# al115v20_power.net
KiCad netlist of a schematic drawn in Altium Designer
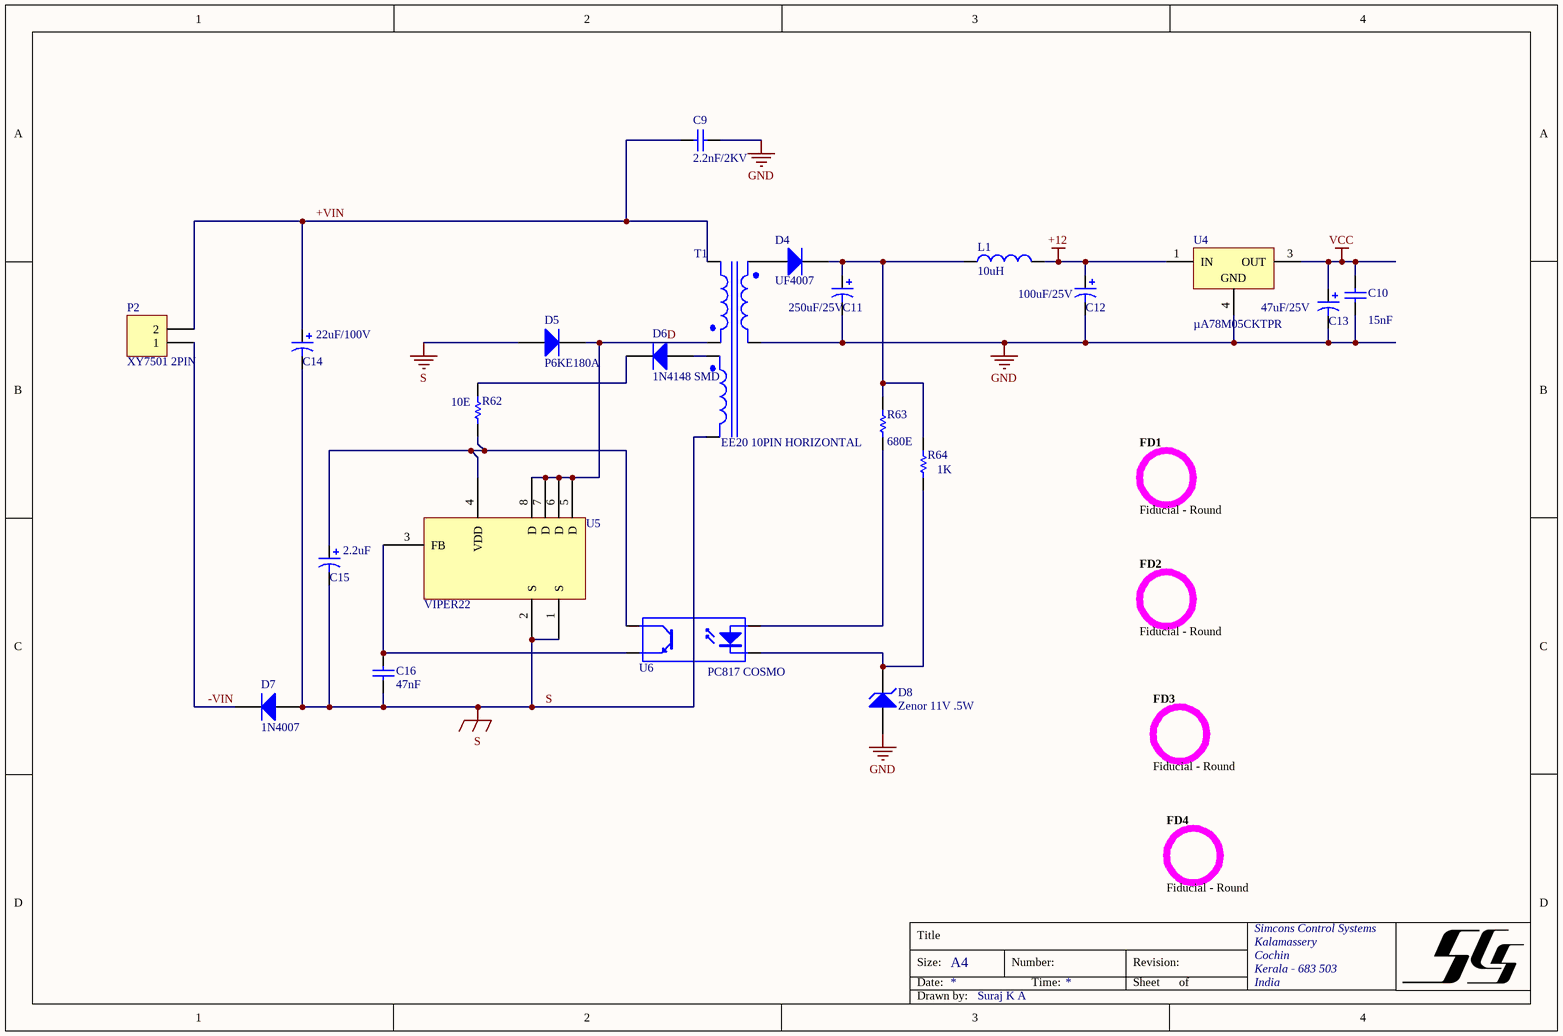
[diagram p0: al115v20_power.SchDoc]

(export (version "E")
  (design (tool "Eeschema 10.0.6"))
  (components
    (comp (ref "C9")
      (value "2.2nF/2KV")
      (footprint "CAP DISC .2")
      (description "Capacitor")
      (fields (field (name "Comment") "2.2nF/2kV") (field (name "PUBLISHER") "Altium Limited"))
      (libsource (lib "Miscellaneous Devices") (part "Cap"))
    )
    (comp (ref "C10")
      (value "15nF")
      (footprint "C1206")
      (description "Capacitor")
      (fields (field (name "Comment") ".1uF 1206") (field (name "PUBLISHER") "Altium Limited"))
      (libsource (lib "Miscellaneous Devices") (part "Cap"))
    )
    (comp (ref "C11")
      (value "250uF/25V")
      (footprint "Cap_.2")
      (description "Polarized Capacitor (Radial)")
      (fields (field (name "Comment") "470uF/25V") (field (name "PUBLISHER") "Altium Limited"))
      (libsource (lib "Miscellaneous Devices") (part "Cap Pol1"))
    )
    (comp (ref "C12")
      (value "100uF/25V")
      (footprint "Cap_.6.3x11x2.5")
      (description "Polarized Capacitor (Radial)")
      (fields (field (name "PUBLISHER") "Altium Limited"))
      (libsource (lib "Miscellaneous Devices") (part "Cap Pol1"))
    )
    (comp (ref "C13")
      (value "47uF/25V")
      (footprint "Cap_.6.3x11x2.5")
      (description "Polarized Capacitor (Radial)")
      (fields (field (name "Comment") "100uF/25V") (field (name "PUBLISHER") "Altium Limited"))
      (libsource (lib "Miscellaneous Devices") (part "Cap Pol1"))
    )
    (comp (ref "C14")
      (value "22uF/100V")
      (footprint "Cap_.2")
      (description "Polarized Capacitor (Radial)")
      (fields (field (name "PUBLISHER") "Altium Limited"))
      (libsource (lib "Miscellaneous Devices") (part "Cap Pol1"))
    )
    (comp (ref "C15")
      (value "2.2uF")
      (footprint "Cap_.1")
      (description "Polarized Capacitor (Radial)")
      (fields (field (name "Comment") "10uF/63V") (field (name "PUBLISHER") "Altium Limited"))
      (libsource (lib "Miscellaneous Devices") (part "Cap Pol1"))
    )
    (comp (ref "C16")
      (value "47nF")
      (footprint "C1206")
      (description "Capacitor")
      (fields (field (name "Comment") "47nF 1206") (field (name "PUBLISHER") "Altium Limited"))
      (libsource (lib "Miscellaneous Devices") (part "Cap"))
    )
    (comp (ref "D4")
      (value "UF4007")
      (footprint "DIODE1A")
      (description "Default Diode")
      (fields (field (name "PUBLISHER") "Altium Limited"))
      (libsource (lib "Miscellaneous Devices") (part "Diode"))
    )
    (comp (ref "D5")
      (value "P6KE180A")
      (footprint "DIODE1A")
      (description "Default Diode")
      (fields (field (name "PUBLISHER") "Altium Limited"))
      (libsource (lib "Miscellaneous Devices") (part "Diode"))
    )
    (comp (ref "D6")
      (value "1N4148 SMD")
      (footprint "4148SMDW")
      (description "Default Diode")
      (fields (field (name "PUBLISHER") "Altium Limited"))
      (libsource (lib "Miscellaneous Devices") (part "Diode"))
    )
    (comp (ref "D7")
      (value "1N4007")
      (footprint "DIODE1A")
      (description "Default Diode")
      (fields (field (name "PUBLISHER") "Altium Limited"))
      (libsource (lib "Miscellaneous Devices") (part "Diode"))
    )
    (comp (ref "D8")
      (value "Zenor 11V .5W")
      (footprint "DZENOR .25W - duplicate")
      (description "Zener Diode")
      (fields (field (name "PUBLISHER") "Altium Limited"))
      (libsource (lib "Miscellaneous Devices") (part "D Zener"))
    )
    (comp (ref "FD1")
      (value "Fiducial - Round")
      (footprint "FIDUCIAL 2mm")
      (description "Fiducial - Round 1.5mm Top-Bottom")
      (libsource (lib "PCB_Project1") (part "FIDUCIAL ROUND"))
    )
    (comp (ref "FD2")
      (value "Fiducial - Round")
      (footprint "FIDUCIAL 2mm")
      (description "Fiducial - Round 1.5mm Top-Bottom")
      (libsource (lib "PCB_Project1") (part "FIDUCIAL ROUND"))
    )
    (comp (ref "FD3")
      (value "Fiducial - Round")
      (footprint "FIDUCIAL 2MM")
      (description "Fiducial - Round 1.5mm Top-Bottom")
      (libsource (lib "PCB_Project1") (part "FIDUCIAL ROUND"))
    )
    (comp (ref "FD4")
      (value "Fiducial - Round")
      (footprint "FIDUCIAL 2MM")
      (description "Fiducial - Round 1.5mm Top-Bottom")
      (libsource (lib "PCB_Project1") (part "FIDUCIAL ROUND"))
    )
    (comp (ref "L1")
      (value "10uH")
      (footprint "INDUCTOR 5x8")
      (description "Inductor")
      (fields (field (name "Comment") "Inductor 10uH Drum Core") (field (name "PUBLISHER") "Altium Limited"))
      (libsource (lib "Miscellaneous Devices") (part "Inductor"))
    )
    (comp (ref "P2")
      (value "XY7501 2PIN")
      (footprint "XY7501_7.62_2PIN")
      (description "Header, 2-Pin")
      (fields (field (name "PUBLISHER") "Altium Limited"))
      (libsource (lib "Miscellaneous Connectors") (part "Header 2"))
    )
    (comp (ref "R62")
      (value "10E")
      (footprint "R1206")
      (description "Semiconductor Resistor")
      (fields (field (name "Comment") "10E 1206") (field (name "PUBLISHER") "Altium Limited"))
      (libsource (lib "Miscellaneous Devices") (part "Res Semi"))
    )
    (comp (ref "R63")
      (value "680E")
      (footprint "R1206")
      (description "Resistor")
      (fields (field (name "Comment") "100E 1206") (field (name "PUBLISHER") "Altium Limited"))
      (libsource (lib "Miscellaneous Devices") (part "Res1"))
    )
    (comp (ref "R64")
      (value "1K")
      (footprint "R1206")
      (description "Resistor")
      (fields (field (name "Comment") "1K 1206") (field (name "PUBLISHER") "Altium Limited"))
      (libsource (lib "Miscellaneous Devices") (part "Res1"))
    )
    (comp (ref "T1")
      (value "EE20 10PIN HORIZONTAL")
      (footprint "EE20_HOR_10PIN")
      (description "Three-winding Transformer (Switching")
      (fields (field (name "PUBLISHER") "Altium Limited"))
      (libsource (lib "PCB_Project1") (part "TransSwitching"))
    )
    (comp (ref "U4")
      (value "µA78M05CKTPR")
      (footprint "TO252AA")
      (description "Positive-Voltage Regulator")
      (fields (field (name "PUBLISHER") "Altium Limited"))
      (libsource (lib "TI Power Mgt Voltage Regulator") (part "µA78M05CKTPR"))
    )
    (comp (ref "U5")
      (value "VIPER22")
      (footprint "DIP-8_S")
      (fields (field (name "MANUFACTURER") "Power Integrations"))
      (libsource (lib "PCB_Project1") (part "VIPER22"))
    )
    (comp (ref "U6")
      (value "PC817 COSMO")
      (footprint "DIP-4_S")
      (description "4-Pin Phototransistor Optocoupler")
      (fields (field (name "PUBLISHER") "Altium Limited"))
      (libsource (lib "Miscellaneous Devices") (part "Optoisolator1"))
    )
  )
  (nets
    (net (code "1") (name "+12") (class "Default")
      (node (ref "C12") (pin "1") (pinfunction "1_1") (pintype "passive"))
      (node (ref "L1") (pin "2") (pinfunction "2_2") (pintype "passive"))
      (node (ref "U4") (pin "1") (pinfunction "IN_1") (pintype "power_in"))
    )
    (net (code "2") (name "/+VIN") (class "Default")
      (node (ref "C14") (pin "1") (pinfunction "1_1") (pintype "passive"))
      (node (ref "C9") (pin "2") (pinfunction "2_2") (pintype "passive"))
      (node (ref "P2") (pin "2") (pinfunction "2_2") (pintype "passive"))
      (node (ref "T1") (pin "1") (pinfunction "Pri+_1") (pintype "passive"))
    )
    (net (code "3") (name "/-VIN") (class "Default")
      (node (ref "D7") (pin "2") (pinfunction "K_2") (pintype "passive"))
      (node (ref "P2") (pin "1") (pinfunction "1_1") (pintype "passive"))
    )
    (net (code "4") (name "/D") (class "Default")
      (node (ref "D5") (pin "2") (pinfunction "K_2") (pintype "passive"))
      (node (ref "T1") (pin "2") (pinfunction "Pri-_2") (pintype "passive"))
      (node (ref "U5") (pin "5") (pinfunction "D_5") (pintype "passive"))
      (node (ref "U5") (pin "6") (pinfunction "D_6") (pintype "passive"))
      (node (ref "U5") (pin "7") (pinfunction "D_7") (pintype "passive"))
      (node (ref "U5") (pin "8") (pinfunction "D_8") (pintype "passive"))
    )
    (net (code "5") (name "GND") (class "Default")
      (node (ref "C10") (pin "1") (pinfunction "1_1") (pintype "passive"))
      (node (ref "C11") (pin "2") (pinfunction "2_2") (pintype "passive"))
      (node (ref "C12") (pin "2") (pinfunction "2_2") (pintype "passive"))
      (node (ref "C13") (pin "2") (pinfunction "2_2") (pintype "passive"))
      (node (ref "C9") (pin "1") (pinfunction "1_1") (pintype "passive"))
      (node (ref "D8") (pin "1") (pinfunction "A_1") (pintype "passive"))
      (node (ref "T1") (pin "7") (pinfunction "Sec1-_7") (pintype "passive"))
      (node (ref "U4") (pin "4") (pinfunction "GND_4") (pintype "power_in"))
    )
    (net (code "6") (name "Net-(D4-A)") (class "Default")
      (node (ref "D4") (pin "1") (pinfunction "A_1") (pintype "passive"))
      (node (ref "T1") (pin "9") (pinfunction "Sec1+_9") (pintype "passive"))
    )
    (net (code "7") (name "Net-(D4-K)") (class "Default")
      (node (ref "C11") (pin "1") (pinfunction "1_1") (pintype "passive"))
      (node (ref "D4") (pin "2") (pinfunction "K_2") (pintype "passive"))
      (node (ref "L1") (pin "1") (pinfunction "1_1") (pintype "passive"))
      (node (ref "R63") (pin "2") (pinfunction "2_2") (pintype "passive"))
      (node (ref "R64") (pin "2") (pinfunction "2_2") (pintype "passive"))
    )
    (net (code "8") (name "Net-(D6-A)") (class "Default")
      (node (ref "D6") (pin "1") (pinfunction "A_1") (pintype "passive"))
      (node (ref "T1") (pin "4") (pinfunction "Sec2-_4") (pintype "passive"))
    )
    (net (code "9") (name "Net-(D6-K)") (class "Default")
      (node (ref "D6") (pin "2") (pinfunction "K_2") (pintype "passive"))
      (node (ref "R62") (pin "2") (pinfunction "2_2") (pintype "passive"))
    )
    (net (code "10") (name "Net-(D8-K)") (class "Default")
      (node (ref "D8") (pin "2") (pinfunction "K_2") (pintype "passive"))
      (node (ref "R64") (pin "1") (pinfunction "1_1") (pintype "passive"))
      (node (ref "U6") (pin "2") (pinfunction "K_2") (pintype "passive"))
    )
    (net (code "11") (name "Net-(U5-FB)") (class "Default")
      (node (ref "C16") (pin "1") (pinfunction "1_1") (pintype "passive"))
      (node (ref "U5") (pin "3") (pinfunction "FB_3") (pintype "passive"))
      (node (ref "U6") (pin "3") (pinfunction "E_3") (pintype "passive"))
    )
    (net (code "12") (name "Net-(U5-VDD)") (class "Default")
      (node (ref "C15") (pin "1") (pinfunction "1_1") (pintype "passive"))
      (node (ref "R62") (pin "1") (pinfunction "1_1") (pintype "passive"))
      (node (ref "U5") (pin "4") (pinfunction "VDD_4") (pintype "passive"))
      (node (ref "U6") (pin "4") (pinfunction "C_4") (pintype "passive"))
    )
    (net (code "13") (name "Net-(U6-A)") (class "Default")
      (node (ref "R63") (pin "1") (pinfunction "1_1") (pintype "passive"))
      (node (ref "U6") (pin "1") (pinfunction "A_1") (pintype "passive"))
    )
    (net (code "14") (name "S") (class "Default")
      (node (ref "C14") (pin "2") (pinfunction "2_2") (pintype "passive"))
      (node (ref "C15") (pin "2") (pinfunction "2_2") (pintype "passive"))
      (node (ref "C16") (pin "2") (pinfunction "2_2") (pintype "passive"))
      (node (ref "D5") (pin "1") (pinfunction "A_1") (pintype "passive"))
      (node (ref "D7") (pin "1") (pinfunction "A_1") (pintype "passive"))
      (node (ref "T1") (pin "5") (pinfunction "Sec2+_5") (pintype "passive"))
      (node (ref "U5") (pin "1") (pinfunction "S_1") (pintype "passive"))
      (node (ref "U5") (pin "2") (pinfunction "S_2") (pintype "passive"))
    )
    (net (code "15") (name "VCC") (class "Default")
      (node (ref "C10") (pin "2") (pinfunction "2_2") (pintype "passive"))
      (node (ref "C13") (pin "1") (pinfunction "1_1") (pintype "passive"))
      (node (ref "U4") (pin "3") (pinfunction "OUT_3") (pintype "power_in"))
    )
  )
)
